# ETH1G_RJ45wLED.net
KiCad netlist of a schematic drawn in Altium Designer
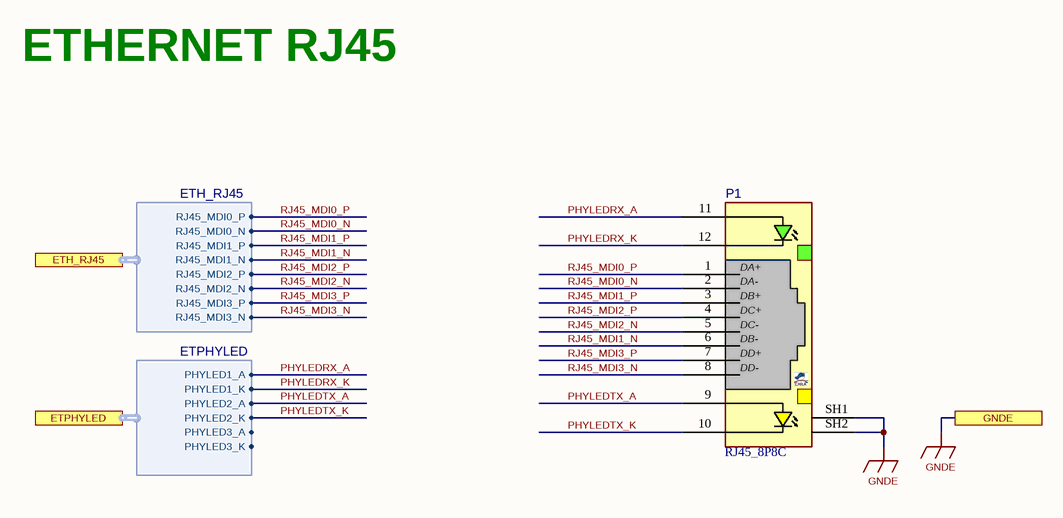
[diagram p0: ETH1G_RJ45wLED.SchDoc]

(export (version "E")
  (design (tool "Eeschema 10.0.6"))
  (components
    (comp (ref "P1")
      (value "RJ45_8P8C")
      (footprint "RJ45_8S_RA_TU_L")
      (description "RJ45, 8P+LED, SHIELDED, RightAngle, TabUP")
      (fields (field (name "MANF") "WURTH") (field (name "MANF_P#") "615008137421"))
      (libsource (lib "conn_rj_ModularJack") (part "RJ45_8S_RA_TU_L"))
    )
  )
  (nets
    (net (code "3") (name "/PHYLEDRX_A") (class "Default")
      (node (ref "P1") (pin "11") (pinfunction "GLED+_11") (pintype "passive"))
    )
    (net (code "4") (name "/PHYLEDRX_K") (class "Default")
      (node (ref "P1") (pin "12") (pinfunction "GLED-_12") (pintype "passive"))
    )
    (net (code "5") (name "/PHYLEDTX_A") (class "Default")
      (node (ref "P1") (pin "9") (pinfunction "YLED+_9") (pintype "passive"))
    )
    (net (code "6") (name "/PHYLEDTX_K") (class "Default")
      (node (ref "P1") (pin "10") (pinfunction "YLED-_10") (pintype "passive"))
    )
    (net (code "7") (name "/RJ45_MDI0_N") (class "Default")
      (node (ref "P1") (pin "2") (pinfunction "DA-_2") (pintype "passive"))
    )
    (net (code "8") (name "/RJ45_MDI0_P") (class "Default")
      (node (ref "P1") (pin "1") (pinfunction "DA+_1") (pintype "passive"))
    )
    (net (code "9") (name "/RJ45_MDI1_N") (class "Default")
      (node (ref "P1") (pin "6") (pinfunction "DB-_6") (pintype "passive"))
    )
    (net (code "10") (name "/RJ45_MDI1_P") (class "Default")
      (node (ref "P1") (pin "3") (pinfunction "DB+_3") (pintype "passive"))
    )
    (net (code "11") (name "/RJ45_MDI2_N") (class "Default")
      (node (ref "P1") (pin "5") (pinfunction "DC-_5") (pintype "passive"))
    )
    (net (code "12") (name "/RJ45_MDI2_P") (class "Default")
      (node (ref "P1") (pin "4") (pinfunction "DC+_4") (pintype "passive"))
    )
    (net (code "13") (name "/RJ45_MDI3_N") (class "Default")
      (node (ref "P1") (pin "8") (pinfunction "DD-_8") (pintype "passive"))
    )
    (net (code "14") (name "/RJ45_MDI3_P") (class "Default")
      (node (ref "P1") (pin "7") (pinfunction "DD+_7") (pintype "passive"))
    )
    (net (code "17") (name "GNDE") (class "Default")
      (node (ref "P1") (pin "SH1") (pinfunction "SH1_SH1") (pintype "passive"))
      (node (ref "P1") (pin "SH2") (pinfunction "SH2_SH2") (pintype "passive"))
    )
  )
)
